# Un_51_2.net
KiCad netlist of a schematic drawn in EAGLE
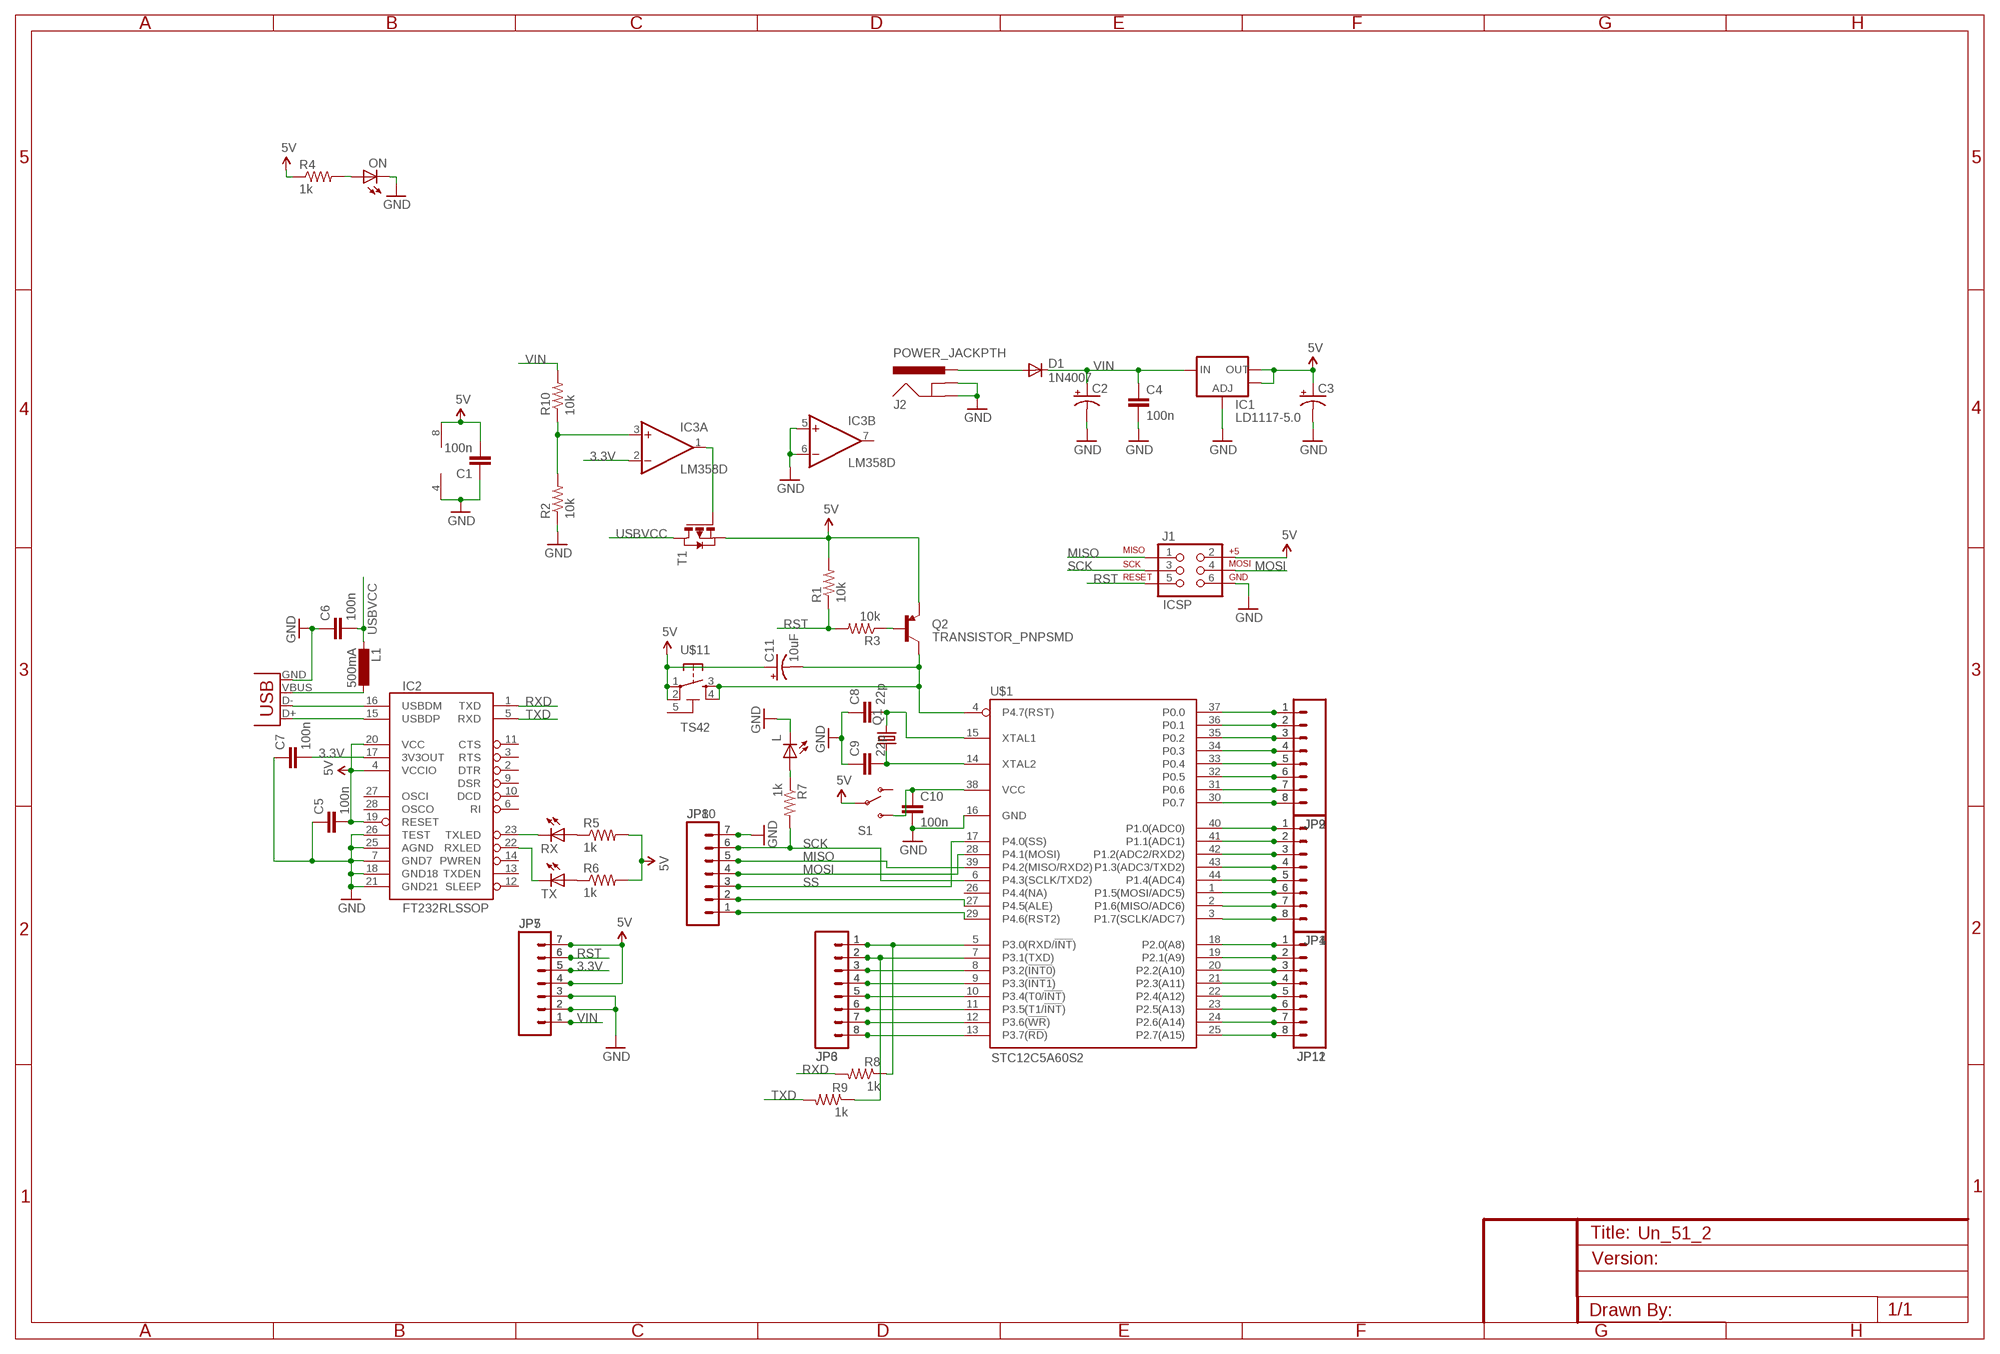
[diagram p0: schematic, sheet 1]

(export (version "E")
  (design (tool "Eeschema 10.0.6"))
  (components
    (comp (ref "C1")
      (value "100n")
      (footprint "eagle-import:0603-CAP")
      (libsource (lib "eagle-import") (part "CAP0603-CAP"))
    )
    (comp (ref "C2")
      (value "CAP_POLD")
      (footprint "eagle-import:PANASONIC_D")
      (libsource (lib "eagle-import") (part "CAP_POLD"))
    )
    (comp (ref "C3")
      (value "CAP_POLD")
      (footprint "eagle-import:PANASONIC_D")
      (libsource (lib "eagle-import") (part "CAP_POLD"))
    )
    (comp (ref "C4")
      (value "100n")
      (footprint "eagle-import:0603-CAP")
      (libsource (lib "eagle-import") (part "CAP0603-CAP"))
    )
    (comp (ref "C5")
      (value "100n")
      (footprint "eagle-import:0603-CAP")
      (libsource (lib "eagle-import") (part "CAP0603-CAP"))
    )
    (comp (ref "C6")
      (value "100n")
      (footprint "eagle-import:0603-CAP")
      (libsource (lib "eagle-import") (part "CAP0603-CAP"))
    )
    (comp (ref "C7")
      (value "100n")
      (footprint "eagle-import:0603-CAP")
      (libsource (lib "eagle-import") (part "CAP0603-CAP"))
    )
    (comp (ref "C8")
      (value "22p")
      (footprint "eagle-import:0805")
      (libsource (lib "eagle-import") (part "CAP0805"))
    )
    (comp (ref "C9")
      (value "22p")
      (footprint "eagle-import:0805")
      (libsource (lib "eagle-import") (part "CAP0805"))
    )
    (comp (ref "C10")
      (value "100n")
      (footprint "eagle-import:0603-CAP")
      (libsource (lib "eagle-import") (part "CAP0603-CAP"))
    )
    (comp (ref "C11")
      (value "10uF")
      (footprint "eagle-import:EIA3216")
      (libsource (lib "eagle-import") (part "CAP_POL1206"))
    )
    (comp (ref "D1")
      (value "1N4007")
      (footprint "eagle-import:SMB")
      (libsource (lib "eagle-import") (part "DIODE-SMB"))
    )
    (comp (ref "IC1")
      (value "LD1117-5.0")
      (footprint "eagle-import:SOT223")
      (libsource (lib "eagle-import") (part "V_REG_LM1117SOT223"))
    )
    (comp (ref "IC2")
      (value "FT232RLSSOP")
      (footprint "eagle-import:SSOP28DB")
      (libsource (lib "eagle-import") (part "FT232RLSSOP"))
    )
    (comp (ref "IC3")
      (value "LM358D")
      (footprint "eagle-import:SO08")
      (libsource (lib "eagle-import") (part "LM358D"))
    )
    (comp (ref "J1")
      (value "ICSP")
      (footprint "eagle-import:2X3")
      (libsource (lib "eagle-import") (part "AVR_SPI_PRG_6PTH"))
    )
    (comp (ref "J2")
      (value "POWER_JACKPTH")
      (footprint "eagle-import:POWER_JACK_PTH")
      (libsource (lib "eagle-import") (part "POWER_JACKPTH"))
    )
    (comp (ref "JP1")
      (value "M081X08")
      (footprint "eagle-import:1X08")
      (libsource (lib "eagle-import") (part "M081X08"))
    )
    (comp (ref "JP2")
      (value "M081X08")
      (footprint "eagle-import:1X08")
      (libsource (lib "eagle-import") (part "M081X08"))
    )
    (comp (ref "JP3")
      (value "M08")
      (footprint "eagle-import:1X08")
      (libsource (lib "eagle-import") (part "M08"))
    )
    (comp (ref "JP4")
      (value "M081X08")
      (footprint "eagle-import:1X08")
      (libsource (lib "eagle-import") (part "M081X08"))
    )
    (comp (ref "JP5")
      (value "M07")
      (footprint "eagle-import:1X07")
      (libsource (lib "eagle-import") (part "M07"))
    )
    (comp (ref "JP6")
      (value "M08")
      (footprint "eagle-import:1X08")
      (libsource (lib "eagle-import") (part "M08"))
    )
    (comp (ref "JP7")
      (value "M07")
      (footprint "eagle-import:1X07")
      (libsource (lib "eagle-import") (part "M07"))
    )
    (comp (ref "JP8")
      (value "M07")
      (footprint "eagle-import:1X07")
      (libsource (lib "eagle-import") (part "M07"))
    )
    (comp (ref "JP9")
      (value "M081X08")
      (footprint "eagle-import:1X08")
      (libsource (lib "eagle-import") (part "M081X08"))
    )
    (comp (ref "JP10")
      (value "M07")
      (footprint "eagle-import:1X07")
      (libsource (lib "eagle-import") (part "M07"))
    )
    (comp (ref "JP11")
      (value "M081X08")
      (footprint "eagle-import:1X08")
      (libsource (lib "eagle-import") (part "M081X08"))
    )
    (comp (ref "JP12")
      (value "M081X08")
      (footprint "eagle-import:1X08")
      (libsource (lib "eagle-import") (part "M081X08"))
    )
    (comp (ref "L")
      (value "LED0805")
      (footprint "eagle-import:LED-0805")
      (libsource (lib "eagle-import") (part "LED0805"))
    )
    (comp (ref "L1")
      (value "500mA")
      (footprint "eagle-import:L1812")
      (libsource (lib "eagle-import") (part "L-EUL1812"))
    )
    (comp (ref "ON")
      (value "LED0805")
      (footprint "eagle-import:LED-0805")
      (libsource (lib "eagle-import") (part "LED0805"))
    )
    (comp (ref "Q1")
      (value "CRYSTALHC49US")
      (footprint "eagle-import:HC49US")
      (libsource (lib "eagle-import") (part "CRYSTALHC49US"))
    )
    (comp (ref "Q2")
      (value "TRANSISTOR_PNPSMD")
      (footprint "eagle-import:SOT23-3")
      (libsource (lib "eagle-import") (part "TRANSISTOR_PNPSMD"))
    )
    (comp (ref "R1")
      (value "10k")
      (footprint "eagle-import:0805")
      (libsource (lib "eagle-import") (part "RESISTOR0805-RES"))
    )
    (comp (ref "R2")
      (value "10k")
      (footprint "eagle-import:0805")
      (libsource (lib "eagle-import") (part "RESISTOR0805-RES"))
    )
    (comp (ref "R3")
      (value "10k")
      (footprint "eagle-import:0805")
      (libsource (lib "eagle-import") (part "RESISTOR0805-RES"))
    )
    (comp (ref "R4")
      (value "1k")
      (footprint "eagle-import:0805")
      (libsource (lib "eagle-import") (part "RESISTOR0805-RES"))
    )
    (comp (ref "R5")
      (value "1k")
      (footprint "eagle-import:0805")
      (libsource (lib "eagle-import") (part "RESISTOR0805-RES"))
    )
    (comp (ref "R6")
      (value "1k")
      (footprint "eagle-import:0805")
      (libsource (lib "eagle-import") (part "RESISTOR0805-RES"))
    )
    (comp (ref "R7")
      (value "1k")
      (footprint "eagle-import:0805")
      (libsource (lib "eagle-import") (part "RESISTOR0805-RES"))
    )
    (comp (ref "R8")
      (value "1k")
      (footprint "eagle-import:0805")
      (libsource (lib "eagle-import") (part "RESISTOR0805-RES"))
    )
    (comp (ref "R9")
      (value "1k")
      (footprint "eagle-import:0805")
      (libsource (lib "eagle-import") (part "RESISTOR0805-RES"))
    )
    (comp (ref "R10")
      (value "10k")
      (footprint "eagle-import:0805")
      (libsource (lib "eagle-import") (part "RESISTOR0805-RES"))
    )
    (comp (ref "RX")
      (value "LED0805")
      (footprint "eagle-import:LED-0805")
      (libsource (lib "eagle-import") (part "LED0805"))
    )
    (comp (ref "S1")
      (value "SWITCH-SPST")
      (footprint "eagle-import:SWITCH-SPDT2")
      (libsource (lib "eagle-import") (part "SWITCH-SPST"))
    )
    (comp (ref "T1")
      (value "PMOSSOT23")
      (footprint "eagle-import:SOT-23")
      (libsource (lib "eagle-import") (part "PMOSSOT23"))
    )
    (comp (ref "TX")
      (value "LED0805")
      (footprint "eagle-import:LED-0805")
      (libsource (lib "eagle-import") (part "LED0805"))
    )
    (comp (ref "U$1")
      (value "STC12C5A60S2")
      (footprint "eagle-import:TQFP44")
      (libsource (lib "eagle-import") (part "STC12C5A60S2"))
    )
    (comp (ref "U$11")
      (value "TS42")
      (footprint "eagle-import:TS42")
      (libsource (lib "eagle-import") (part "TS42"))
    )
    (comp (ref "X1")
      (value "USBPTH")
      (footprint "eagle-import:USB-B-PTH")
      (libsource (lib "eagle-import") (part "USBPTH"))
    )
  )
  (nets
    (net (code "1") (name "/3.3V") (class "Default")
      (node (ref "C7") (pin "2") (pinfunction "2_2") (pintype "passive"))
      (node (ref "IC2") (pin "17") (pinfunction "3V3OUT_17") (pintype "output"))
      (node (ref "IC3") (pin "2") (pinfunction "-IN_2") (pintype "input"))
      (node (ref "JP5") (pin "5") (pinfunction "5_5") (pintype "passive"))
      (node (ref "JP7") (pin "5") (pinfunction "5_5") (pintype "passive"))
    )
    (net (code "2") (name "/MISO") (class "Default")
      (node (ref "J1") (pin "1") (pinfunction "1_1") (pintype "passive"))
      (node (ref "JP10") (pin "5") (pinfunction "5_5") (pintype "passive"))
      (node (ref "JP8") (pin "5") (pinfunction "5_5") (pintype "passive"))
      (node (ref "U$1") (pin "39") (pinfunction "P4.2(MISO/RXD2)_39") (pintype "bidirectional"))
    )
    (net (code "3") (name "/MOSI") (class "Default")
      (node (ref "J1") (pin "4") (pinfunction "4_4") (pintype "passive"))
      (node (ref "JP10") (pin "4") (pinfunction "4_4") (pintype "passive"))
      (node (ref "JP8") (pin "4") (pinfunction "4_4") (pintype "passive"))
      (node (ref "U$1") (pin "28") (pinfunction "P4.1(MOSI)_28") (pintype "bidirectional"))
    )
    (net (code "4") (name "/RST") (class "Default")
      (node (ref "J1") (pin "5") (pinfunction "5_5") (pintype "passive"))
      (node (ref "JP5") (pin "6") (pinfunction "6_6") (pintype "passive"))
      (node (ref "JP7") (pin "6") (pinfunction "6_6") (pintype "passive"))
      (node (ref "R1") (pin "1") (pinfunction "1_1") (pintype "passive"))
      (node (ref "R3") (pin "2") (pinfunction "2_2") (pintype "passive"))
    )
    (net (code "5") (name "/RXD") (class "Default")
      (node (ref "IC2") (pin "1") (pinfunction "TXD_1") (pintype "output"))
      (node (ref "R8") (pin "2") (pinfunction "2_2") (pintype "passive"))
    )
    (net (code "6") (name "/SCK") (class "Default")
      (node (ref "J1") (pin "3") (pinfunction "3_3") (pintype "passive"))
      (node (ref "JP10") (pin "6") (pinfunction "6_6") (pintype "passive"))
      (node (ref "JP8") (pin "6") (pinfunction "6_6") (pintype "passive"))
      (node (ref "R7") (pin "2") (pinfunction "2_2") (pintype "passive"))
      (node (ref "U$1") (pin "6") (pinfunction "P4.3(SCLK/TXD2)_6") (pintype "bidirectional"))
    )
    (net (code "7") (name "/SS") (class "Default")
      (node (ref "JP10") (pin "3") (pinfunction "3_3") (pintype "passive"))
      (node (ref "JP8") (pin "3") (pinfunction "3_3") (pintype "passive"))
      (node (ref "U$1") (pin "17") (pinfunction "P4.0(SS)_17") (pintype "bidirectional"))
    )
    (net (code "8") (name "/TXD") (class "Default")
      (node (ref "IC2") (pin "5") (pinfunction "RXD_5") (pintype "input"))
      (node (ref "R9") (pin "2") (pinfunction "2_2") (pintype "passive"))
    )
    (net (code "9") (name "/USBVCC") (class "Default")
      (node (ref "C6") (pin "2") (pinfunction "2_2") (pintype "passive"))
      (node (ref "L1") (pin "2") (pinfunction "2_2") (pintype "passive"))
      (node (ref "T1") (pin "1") (pinfunction "D_1") (pintype "passive"))
    )
    (net (code "10") (name "/VIN") (class "Default")
      (node (ref "C2") (pin "+") (pinfunction "+_+") (pintype "passive"))
      (node (ref "C4") (pin "1") (pinfunction "1_1") (pintype "passive"))
      (node (ref "D1") (pin "C") (pinfunction "C_C") (pintype "passive"))
      (node (ref "IC1") (pin "3") (pinfunction "IN_3") (pintype "input"))
      (node (ref "JP5") (pin "1") (pinfunction "1_1") (pintype "passive"))
      (node (ref "JP7") (pin "1") (pinfunction "1_1") (pintype "passive"))
      (node (ref "R10") (pin "2") (pinfunction "2_2") (pintype "passive"))
    )
    (net (code "11") (name "5V") (class "Default")
      (node (ref "C1") (pin "2") (pinfunction "2_2") (pintype "passive"))
      (node (ref "C11") (pin "A") (pinfunction "+_A") (pintype "passive"))
      (node (ref "C3") (pin "+") (pinfunction "+_+") (pintype "passive"))
      (node (ref "C5") (pin "2") (pinfunction "2_2") (pintype "passive"))
      (node (ref "IC1") (pin "2") (pinfunction "OUT_2") (pintype "output"))
      (node (ref "IC1") (pin "4") (pinfunction "OUT_4") (pintype "output"))
      (node (ref "IC2") (pin "19") (pinfunction "RESET_19") (pintype "input"))
      (node (ref "IC2") (pin "20") (pinfunction "VCC_20") (pintype "power_in"))
      (node (ref "IC2") (pin "4") (pinfunction "VCCIO_4") (pintype "power_in"))
      (node (ref "IC3") (pin "8") (pinfunction "V+_8") (pintype "power_in"))
      (node (ref "J1") (pin "2") (pinfunction "2_2") (pintype "passive"))
      (node (ref "JP5") (pin "4") (pinfunction "4_4") (pintype "passive"))
      (node (ref "JP5") (pin "7") (pinfunction "7_7") (pintype "passive"))
      (node (ref "JP7") (pin "4") (pinfunction "4_4") (pintype "passive"))
      (node (ref "JP7") (pin "7") (pinfunction "7_7") (pintype "passive"))
      (node (ref "Q2") (pin "2") (pinfunction "E_2") (pintype "passive"))
      (node (ref "R1") (pin "2") (pinfunction "2_2") (pintype "passive"))
      (node (ref "R4") (pin "1") (pinfunction "1_1") (pintype "passive"))
      (node (ref "R5") (pin "2") (pinfunction "2_2") (pintype "passive"))
      (node (ref "R6") (pin "2") (pinfunction "2_2") (pintype "passive"))
      (node (ref "S1") (pin "2") (pinfunction "P_2") (pintype "passive"))
      (node (ref "T1") (pin "2") (pinfunction "S_2") (pintype "passive"))
      (node (ref "U$11") (pin "1") (pinfunction "1_1") (pintype "passive"))
      (node (ref "U$11") (pin "2") (pinfunction "2_2") (pintype "passive"))
    )
    (net (code "12") (name "GND") (class "Default")
      (node (ref "C1") (pin "1") (pinfunction "1_1") (pintype "passive"))
      (node (ref "C10") (pin "2") (pinfunction "2_2") (pintype "passive"))
      (node (ref "C2") (pin "-") (pinfunction "-_-") (pintype "passive"))
      (node (ref "C3") (pin "-") (pinfunction "-_-") (pintype "passive"))
      (node (ref "C4") (pin "2") (pinfunction "2_2") (pintype "passive"))
      (node (ref "C5") (pin "1") (pinfunction "1_1") (pintype "passive"))
      (node (ref "C6") (pin "1") (pinfunction "1_1") (pintype "passive"))
      (node (ref "C7") (pin "1") (pinfunction "1_1") (pintype "passive"))
      (node (ref "C8") (pin "1") (pinfunction "1_1") (pintype "passive"))
      (node (ref "C9") (pin "1") (pinfunction "1_1") (pintype "passive"))
      (node (ref "IC1") (pin "1") (pinfunction "ADJ_1") (pintype "input"))
      (node (ref "IC2") (pin "18") (pinfunction "GND18_18") (pintype "power_in"))
      (node (ref "IC2") (pin "21") (pinfunction "GND21_21") (pintype "power_in"))
      (node (ref "IC2") (pin "25") (pinfunction "AGND_25") (pintype "power_in"))
      (node (ref "IC2") (pin "26") (pinfunction "TEST_26") (pintype "input"))
      (node (ref "IC2") (pin "7") (pinfunction "GND7_7") (pintype "power_in"))
      (node (ref "IC3") (pin "4") (pinfunction "V-_4") (pintype "power_in"))
      (node (ref "IC3") (pin "5") (pinfunction "+IN_5") (pintype "input"))
      (node (ref "IC3") (pin "6") (pinfunction "-IN_6") (pintype "input"))
      (node (ref "J1") (pin "6") (pinfunction "6_6") (pintype "passive"))
      (node (ref "J2") (pin "GND") (pinfunction "GND_GND") (pintype "bidirectional"))
      (node (ref "J2") (pin "GNDBREAK") (pinfunction "GNDBREAK_GNDBREAK") (pintype "bidirectional"))
      (node (ref "JP10") (pin "7") (pinfunction "7_7") (pintype "passive"))
      (node (ref "JP5") (pin "2") (pinfunction "2_2") (pintype "passive"))
      (node (ref "JP5") (pin "3") (pinfunction "3_3") (pintype "passive"))
      (node (ref "JP7") (pin "2") (pinfunction "2_2") (pintype "passive"))
      (node (ref "JP7") (pin "3") (pinfunction "3_3") (pintype "passive"))
      (node (ref "JP8") (pin "7") (pinfunction "7_7") (pintype "passive"))
      (node (ref "L") (pin "2") (pinfunction "C_2") (pintype "passive"))
      (node (ref "ON") (pin "2") (pinfunction "C_2") (pintype "passive"))
      (node (ref "R2") (pin "1") (pinfunction "1_1") (pintype "passive"))
      (node (ref "U$1") (pin "16") (pinfunction "GND_16") (pintype "bidirectional"))
      (node (ref "X1") (pin "GND") (pinfunction "GND_GND") (pintype "bidirectional"))
    )
    (net (code "13") (name "Net-(C11--)") (class "Default")
      (node (ref "C11") (pin "C") (pinfunction "-_C") (pintype "passive"))
      (node (ref "Q2") (pin "3") (pinfunction "C_3") (pintype "passive"))
      (node (ref "U$1") (pin "4") (pinfunction "P4.7(RST)_4") (pintype "bidirectional"))
      (node (ref "U$11") (pin "3") (pinfunction "3_3") (pintype "passive"))
      (node (ref "U$11") (pin "4") (pinfunction "4_4") (pintype "passive"))
    )
    (net (code "14") (name "Net-(D1-PadA)") (class "Default")
      (node (ref "D1") (pin "A") (pinfunction "A_A") (pintype "passive"))
      (node (ref "J2") (pin "PWR") (pinfunction "PWR_PWR") (pintype "bidirectional"))
    )
    (net (code "15") (name "Net-(IC2-RXLED)") (class "Default")
      (node (ref "IC2") (pin "22") (pinfunction "RXLED_22") (pintype "input"))
      (node (ref "TX") (pin "2") (pinfunction "C_2") (pintype "passive"))
    )
    (net (code "16") (name "Net-(IC2-TXLED)") (class "Default")
      (node (ref "IC2") (pin "23") (pinfunction "TXLED_23") (pintype "input"))
      (node (ref "RX") (pin "2") (pinfunction "C_2") (pintype "passive"))
    )
    (net (code "17") (name "Net-(IC2-USBDM)") (class "Default")
      (node (ref "IC2") (pin "16") (pinfunction "USBDM_16") (pintype "bidirectional"))
      (node (ref "X1") (pin "D-") (pinfunction "D-_D-") (pintype "bidirectional"))
    )
    (net (code "18") (name "Net-(IC2-USBDP)") (class "Default")
      (node (ref "IC2") (pin "15") (pinfunction "USBDP_15") (pintype "bidirectional"))
      (node (ref "X1") (pin "D+") (pinfunction "D+_D+") (pintype "bidirectional"))
    )
    (net (code "19") (name "Net-(IC3A-+IN)") (class "Default")
      (node (ref "IC3") (pin "3") (pinfunction "+IN_3") (pintype "input"))
      (node (ref "R10") (pin "1") (pinfunction "1_1") (pintype "passive"))
      (node (ref "R2") (pin "2") (pinfunction "2_2") (pintype "passive"))
    )
    (net (code "20") (name "Net-(IC3A-OUT)") (class "Default")
      (node (ref "IC3") (pin "1") (pinfunction "OUT_1") (pintype "output"))
      (node (ref "T1") (pin "3") (pinfunction "G_3") (pintype "passive"))
    )
    (net (code "21") (name "Net-(L-A)") (class "Default")
      (node (ref "L") (pin "1") (pinfunction "A_1") (pintype "passive"))
      (node (ref "R7") (pin "1") (pinfunction "1_1") (pintype "passive"))
    )
    (net (code "22") (name "Net-(L1-Pad1)") (class "Default")
      (node (ref "L1") (pin "1") (pinfunction "1_1") (pintype "passive"))
      (node (ref "X1") (pin "VBUS") (pinfunction "VBUS_VBUS") (pintype "bidirectional"))
    )
    (net (code "23") (name "Net-(ON-A)") (class "Default")
      (node (ref "ON") (pin "1") (pinfunction "A_1") (pintype "passive"))
      (node (ref "R4") (pin "2") (pinfunction "2_2") (pintype "passive"))
    )
    (net (code "24") (name "Net-(Q2-B)") (class "Default")
      (node (ref "Q2") (pin "1") (pinfunction "B_1") (pintype "passive"))
      (node (ref "R3") (pin "1") (pinfunction "1_1") (pintype "passive"))
    )
    (net (code "25") (name "Net-(RX-A)") (class "Default")
      (node (ref "R5") (pin "1") (pinfunction "1_1") (pintype "passive"))
      (node (ref "RX") (pin "1") (pinfunction "A_1") (pintype "passive"))
    )
    (net (code "26") (name "Net-(S1-S)") (class "Default")
      (node (ref "C10") (pin "1") (pinfunction "1_1") (pintype "passive"))
      (node (ref "S1") (pin "3") (pinfunction "S_3") (pintype "passive"))
      (node (ref "U$1") (pin "38") (pinfunction "VCC_38") (pintype "bidirectional"))
    )
    (net (code "27") (name "Net-(TX-A)") (class "Default")
      (node (ref "R6") (pin "1") (pinfunction "1_1") (pintype "passive"))
      (node (ref "TX") (pin "1") (pinfunction "A_1") (pintype "passive"))
    )
    (net (code "28") (name "Net-(U$1-P0.0)") (class "Default")
      (node (ref "JP2") (pin "1") (pinfunction "1_1") (pintype "passive"))
      (node (ref "JP9") (pin "1") (pinfunction "1_1") (pintype "passive"))
      (node (ref "U$1") (pin "37") (pinfunction "P0.0_37") (pintype "bidirectional"))
    )
    (net (code "29") (name "Net-(U$1-P0.1)") (class "Default")
      (node (ref "JP2") (pin "2") (pinfunction "2_2") (pintype "passive"))
      (node (ref "JP9") (pin "2") (pinfunction "2_2") (pintype "passive"))
      (node (ref "U$1") (pin "36") (pinfunction "P0.1_36") (pintype "bidirectional"))
    )
    (net (code "30") (name "Net-(U$1-P0.2)") (class "Default")
      (node (ref "JP2") (pin "3") (pinfunction "3_3") (pintype "passive"))
      (node (ref "JP9") (pin "3") (pinfunction "3_3") (pintype "passive"))
      (node (ref "U$1") (pin "35") (pinfunction "P0.2_35") (pintype "bidirectional"))
    )
    (net (code "31") (name "Net-(U$1-P0.3)") (class "Default")
      (node (ref "JP2") (pin "4") (pinfunction "4_4") (pintype "passive"))
      (node (ref "JP9") (pin "4") (pinfunction "4_4") (pintype "passive"))
      (node (ref "U$1") (pin "34") (pinfunction "P0.3_34") (pintype "bidirectional"))
    )
    (net (code "32") (name "Net-(U$1-P0.4)") (class "Default")
      (node (ref "JP2") (pin "5") (pinfunction "5_5") (pintype "passive"))
      (node (ref "JP9") (pin "5") (pinfunction "5_5") (pintype "passive"))
      (node (ref "U$1") (pin "33") (pinfunction "P0.4_33") (pintype "bidirectional"))
    )
    (net (code "33") (name "Net-(U$1-P0.5)") (class "Default")
      (node (ref "JP2") (pin "6") (pinfunction "6_6") (pintype "passive"))
      (node (ref "JP9") (pin "6") (pinfunction "6_6") (pintype "passive"))
      (node (ref "U$1") (pin "32") (pinfunction "P0.5_32") (pintype "bidirectional"))
    )
    (net (code "34") (name "Net-(U$1-P0.6)") (class "Default")
      (node (ref "JP2") (pin "7") (pinfunction "7_7") (pintype "passive"))
      (node (ref "JP9") (pin "7") (pinfunction "7_7") (pintype "passive"))
      (node (ref "U$1") (pin "31") (pinfunction "P0.6_31") (pintype "bidirectional"))
    )
    (net (code "35") (name "Net-(U$1-P0.7)") (class "Default")
      (node (ref "JP2") (pin "8") (pinfunction "8_8") (pintype "passive"))
      (node (ref "JP9") (pin "8") (pinfunction "8_8") (pintype "passive"))
      (node (ref "U$1") (pin "30") (pinfunction "P0.7_30") (pintype "bidirectional"))
    )
    (net (code "36") (name "Net-(U$1-P1.0(ADC0))") (class "Default")
      (node (ref "JP1") (pin "1") (pinfunction "1_1") (pintype "passive"))
      (node (ref "JP4") (pin "1") (pinfunction "1_1") (pintype "passive"))
      (node (ref "U$1") (pin "40") (pinfunction "P1.0(ADC0)_40") (pintype "bidirectional"))
    )
    (net (code "37") (name "Net-(U$1-P1.1(ADC1))") (class "Default")
      (node (ref "JP1") (pin "2") (pinfunction "2_2") (pintype "passive"))
      (node (ref "JP4") (pin "2") (pinfunction "2_2") (pintype "passive"))
      (node (ref "U$1") (pin "41") (pinfunction "P1.1(ADC1)_41") (pintype "bidirectional"))
    )
    (net (code "38") (name "Net-(U$1-P1.2(ADC2{slash}RXD2))") (class "Default")
      (node (ref "JP1") (pin "3") (pinfunction "3_3") (pintype "passive"))
      (node (ref "JP4") (pin "3") (pinfunction "3_3") (pintype "passive"))
      (node (ref "U$1") (pin "42") (pinfunction "P1.2(ADC2/RXD2)_42") (pintype "bidirectional"))
    )
    (net (code "39") (name "Net-(U$1-P1.3(ADC3{slash}TXD2))") (class "Default")
      (node (ref "JP1") (pin "4") (pinfunction "4_4") (pintype "passive"))
      (node (ref "JP4") (pin "4") (pinfunction "4_4") (pintype "passive"))
      (node (ref "U$1") (pin "43") (pinfunction "P1.3(ADC3/TXD2)_43") (pintype "bidirectional"))
    )
    (net (code "40") (name "Net-(U$1-P1.4(ADC4))") (class "Default")
      (node (ref "JP1") (pin "5") (pinfunction "5_5") (pintype "passive"))
      (node (ref "JP4") (pin "5") (pinfunction "5_5") (pintype "passive"))
      (node (ref "U$1") (pin "44") (pinfunction "P1.4(ADC4)_44") (pintype "bidirectional"))
    )
    (net (code "41") (name "Net-(U$1-P1.5(MOSI{slash}ADC5))") (class "Default")
      (node (ref "JP1") (pin "6") (pinfunction "6_6") (pintype "passive"))
      (node (ref "JP4") (pin "6") (pinfunction "6_6") (pintype "passive"))
      (node (ref "U$1") (pin "1") (pinfunction "P1.5(MOSI/ADC5)_1") (pintype "bidirectional"))
    )
    (net (code "42") (name "Net-(U$1-P1.6(MISO{slash}ADC6))") (class "Default")
      (node (ref "JP1") (pin "7") (pinfunction "7_7") (pintype "passive"))
      (node (ref "JP4") (pin "7") (pinfunction "7_7") (pintype "passive"))
      (node (ref "U$1") (pin "2") (pinfunction "P1.6(MISO/ADC6)_2") (pintype "bidirectional"))
    )
    (net (code "43") (name "Net-(U$1-P1.7(SCLK{slash}ADC7))") (class "Default")
      (node (ref "JP1") (pin "8") (pinfunction "8_8") (pintype "passive"))
      (node (ref "JP4") (pin "8") (pinfunction "8_8") (pintype "passive"))
      (node (ref "U$1") (pin "3") (pinfunction "P1.7(SCLK/ADC7)_3") (pintype "bidirectional"))
    )
    (net (code "44") (name "Net-(U$1-P2.0(A8))") (class "Default")
      (node (ref "JP11") (pin "1") (pinfunction "1_1") (pintype "passive"))
      (node (ref "JP12") (pin "1") (pinfunction "1_1") (pintype "passive"))
      (node (ref "U$1") (pin "18") (pinfunction "P2.0(A8)_18") (pintype "bidirectional"))
    )
    (net (code "45") (name "Net-(U$1-P2.1(A9))") (class "Default")
      (node (ref "JP11") (pin "2") (pinfunction "2_2") (pintype "passive"))
      (node (ref "JP12") (pin "2") (pinfunction "2_2") (pintype "passive"))
      (node (ref "U$1") (pin "19") (pinfunction "P2.1(A9)_19") (pintype "bidirectional"))
    )
    (net (code "46") (name "Net-(U$1-P2.2(A10))") (class "Default")
      (node (ref "JP11") (pin "3") (pinfunction "3_3") (pintype "passive"))
      (node (ref "JP12") (pin "3") (pinfunction "3_3") (pintype "passive"))
      (node (ref "U$1") (pin "20") (pinfunction "P2.2(A10)_20") (pintype "bidirectional"))
    )
    (net (code "47") (name "Net-(U$1-P2.3(A11))") (class "Default")
      (node (ref "JP11") (pin "4") (pinfunction "4_4") (pintype "passive"))
      (node (ref "JP12") (pin "4") (pinfunction "4_4") (pintype "passive"))
      (node (ref "U$1") (pin "21") (pinfunction "P2.3(A11)_21") (pintype "bidirectional"))
    )
    (net (code "48") (name "Net-(U$1-P2.4(A12))") (class "Default")
      (node (ref "JP11") (pin "5") (pinfunction "5_5") (pintype "passive"))
      (node (ref "JP12") (pin "5") (pinfunction "5_5") (pintype "passive"))
      (node (ref "U$1") (pin "22") (pinfunction "P2.4(A12)_22") (pintype "bidirectional"))
    )
    (net (code "49") (name "Net-(U$1-P2.5(A13))") (class "Default")
      (node (ref "JP11") (pin "6") (pinfunction "6_6") (pintype "passive"))
      (node (ref "JP12") (pin "6") (pinfunction "6_6") (pintype "passive"))
      (node (ref "U$1") (pin "23") (pinfunction "P2.5(A13)_23") (pintype "bidirectional"))
    )
    (net (code "50") (name "Net-(U$1-P2.6(A14))") (class "Default")
      (node (ref "JP11") (pin "7") (pinfunction "7_7") (pintype "passive"))
      (node (ref "JP12") (pin "7") (pinfunction "7_7") (pintype "passive"))
      (node (ref "U$1") (pin "24") (pinfunction "P2.6(A14)_24") (pintype "bidirectional"))
    )
    (net (code "51") (name "Net-(U$1-P2.7(A15))") (class "Default")
      (node (ref "JP11") (pin "8") (pinfunction "8_8") (pintype "passive"))
      (node (ref "JP12") (pin "8") (pinfunction "8_8") (pintype "passive"))
      (node (ref "U$1") (pin "25") (pinfunction "P2.7(A15)_25") (pintype "bidirectional"))
    )
    (net (code "52") (name "Net-(U$1-P3.0(RXD{slash}~{INT}))") (class "Default")
      (node (ref "JP3") (pin "1") (pinfunction "1_1") (pintype "passive"))
      (node (ref "JP6") (pin "1") (pinfunction "1_1") (pintype "passive"))
      (node (ref "R8") (pin "1") (pinfunction "1_1") (pintype "passive"))
      (node (ref "U$1") (pin "5") (pinfunction "P3.0(RXD/~{INT})_5") (pintype "bidirectional"))
    )
    (net (code "53") (name "Net-(U$1-P3.1(TXD))") (class "Default")
      (node (ref "JP3") (pin "2") (pinfunction "2_2") (pintype "passive"))
      (node (ref "JP6") (pin "2") (pinfunction "2_2") (pintype "passive"))
      (node (ref "R9") (pin "1") (pinfunction "1_1") (pintype "passive"))
      (node (ref "U$1") (pin "7") (pinfunction "P3.1(TXD)_7") (pintype "bidirectional"))
    )
    (net (code "54") (name "Net-(U$1-P3.2(~{INT0}))") (class "Default")
      (node (ref "JP3") (pin "3") (pinfunction "3_3") (pintype "passive"))
      (node (ref "JP6") (pin "3") (pinfunction "3_3") (pintype "passive"))
      (node (ref "U$1") (pin "8") (pinfunction "P3.2(~{INT0})_8") (pintype "bidirectional"))
    )
    (net (code "55") (name "Net-(U$1-P3.3(~{INT1}))") (class "Default")
      (node (ref "JP3") (pin "4") (pinfunction "4_4") (pintype "passive"))
      (node (ref "JP6") (pin "4") (pinfunction "4_4") (pintype "passive"))
      (node (ref "U$1") (pin "9") (pinfunction "P3.3(~{INT1})_9") (pintype "bidirectional"))
    )
    (net (code "56") (name "Net-(U$1-P3.4(T0{slash}~{INT}))") (class "Default")
      (node (ref "JP3") (pin "5") (pinfunction "5_5") (pintype "passive"))
      (node (ref "JP6") (pin "5") (pinfunction "5_5") (pintype "passive"))
      (node (ref "U$1") (pin "10") (pinfunction "P3.4(T0/~{INT})_10") (pintype "bidirectional"))
    )
    (net (code "57") (name "Net-(U$1-P3.5(T1{slash}~{INT}))") (class "Default")
      (node (ref "JP3") (pin "6") (pinfunction "6_6") (pintype "passive"))
      (node (ref "JP6") (pin "6") (pinfunction "6_6") (pintype "passive"))
      (node (ref "U$1") (pin "11") (pinfunction "P3.5(T1/~{INT})_11") (pintype "bidirectional"))
    )
    (net (code "58") (name "Net-(U$1-P3.6(~{WR}))") (class "Default")
      (node (ref "JP3") (pin "7") (pinfunction "7_7") (pintype "passive"))
      (node (ref "JP6") (pin "7") (pinfunction "7_7") (pintype "passive"))
      (node (ref "U$1") (pin "12") (pinfunction "P3.6(~{WR})_12") (pintype "bidirectional"))
    )
    (net (code "59") (name "Net-(U$1-P3.7(~{RD}))") (class "Default")
      (node (ref "JP3") (pin "8") (pinfunction "8_8") (pintype "passive"))
      (node (ref "JP6") (pin "8") (pinfunction "8_8") (pintype "passive"))
      (node (ref "U$1") (pin "13") (pinfunction "P3.7(~{RD})_13") (pintype "bidirectional"))
    )
    (net (code "60") (name "Net-(U$1-P4.5(ALE))") (class "Default")
      (node (ref "JP10") (pin "2") (pinfunction "2_2") (pintype "passive"))
      (node (ref "JP8") (pin "2") (pinfunction "2_2") (pintype "passive"))
      (node (ref "U$1") (pin "27") (pinfunction "P4.5(ALE)_27") (pintype "bidirectional"))
    )
    (net (code "61") (name "Net-(U$1-P4.6(RST2))") (class "Default")
      (node (ref "JP10") (pin "1") (pinfunction "1_1") (pintype "passive"))
      (node (ref "JP8") (pin "1") (pinfunction "1_1") (pintype "passive"))
      (node (ref "U$1") (pin "29") (pinfunction "P4.6(RST2)_29") (pintype "bidirectional"))
    )
    (net (code "62") (name "Net-(U$1-XTAL1)") (class "Default")
      (node (ref "C8") (pin "2") (pinfunction "2_2") (pintype "passive"))
      (node (ref "Q1") (pin "2") (pinfunction "2_2") (pintype "passive"))
      (node (ref "U$1") (pin "15") (pinfunction "XTAL1_15") (pintype "bidirectional"))
    )
    (net (code "63") (name "Net-(U$1-XTAL2)") (class "Default")
      (node (ref "C9") (pin "2") (pinfunction "2_2") (pintype "passive"))
      (node (ref "Q1") (pin "1") (pinfunction "1_1") (pintype "passive"))
      (node (ref "U$1") (pin "14") (pinfunction "XTAL2_14") (pintype "bidirectional"))
    )
    (net (code "64") (name "unconnected-(IC2-CTS-Pad11)") (class "Default")
      (node (ref "IC2") (pin "11") (pinfunction "CTS_11") (pintype "input"))
    )
    (net (code "65") (name "unconnected-(IC2-DCD-Pad10)") (class "Default")
      (node (ref "IC2") (pin "10") (pinfunction "DCD_10") (pintype "input"))
    )
    (net (code "66") (name "unconnected-(IC2-DSR-Pad9)") (class "Default")
      (node (ref "IC2") (pin "9") (pinfunction "DSR_9") (pintype "input"))
    )
    (net (code "67") (name "unconnected-(IC2-DTR-Pad2)") (class "Default")
      (node (ref "IC2") (pin "2") (pinfunction "DTR_2") (pintype "output"))
    )
    (net (code "68") (name "unconnected-(IC2-OSCI-Pad27)") (class "Default")
      (node (ref "IC2") (pin "27") (pinfunction "OSCI_27") (pintype "input"))
    )
    (net (code "69") (name "unconnected-(IC2-OSCO-Pad28)") (class "Default")
      (node (ref "IC2") (pin "28") (pinfunction "OSCO_28") (pintype "output"))
    )
    (net (code "70") (name "unconnected-(IC2-PWREN-Pad14)") (class "Default")
      (node (ref "IC2") (pin "14") (pinfunction "PWREN_14") (pintype "input"))
    )
    (net (code "71") (name "unconnected-(IC2-RI-Pad6)") (class "Default")
      (node (ref "IC2") (pin "6") (pinfunction "RI_6") (pintype "input"))
    )
    (net (code "72") (name "unconnected-(IC2-RTS-Pad3)") (class "Default")
      (node (ref "IC2") (pin "3") (pinfunction "RTS_3") (pintype "output"))
    )
    (net (code "73") (name "unconnected-(IC2-SLEEP-Pad12)") (class "Default")
      (node (ref "IC2") (pin "12") (pinfunction "SLEEP_12") (pintype "input"))
    )
    (net (code "74") (name "unconnected-(IC2-TXDEN-Pad13)") (class "Default")
      (node (ref "IC2") (pin "13") (pinfunction "TXDEN_13") (pintype "input"))
    )
    (net (code "75") (name "unconnected-(IC3B-OUT-Pad7)") (class "Default")
      (node (ref "IC3") (pin "7") (pinfunction "OUT_7") (pintype "output"))
    )
    (net (code "76") (name "unconnected-(S1-O-Pad1)") (class "Default")
      (node (ref "S1") (pin "1") (pinfunction "O_1") (pintype "passive"))
    )
    (net (code "77") (name "unconnected-(U$1-P4.4(NA)-Pad26)") (class "Default")
      (node (ref "U$1") (pin "26") (pinfunction "P4.4(NA)_26") (pintype "bidirectional"))
    )
    (net (code "78") (name "unconnected-(U$11-Pad5)") (class "Default")
      (node (ref "U$11") (pin "5") (pinfunction "5_5") (pintype "passive"))
    )
  )
)
